# ledstripes.net
KiCad netlist of a schematic drawn in Altium Designer
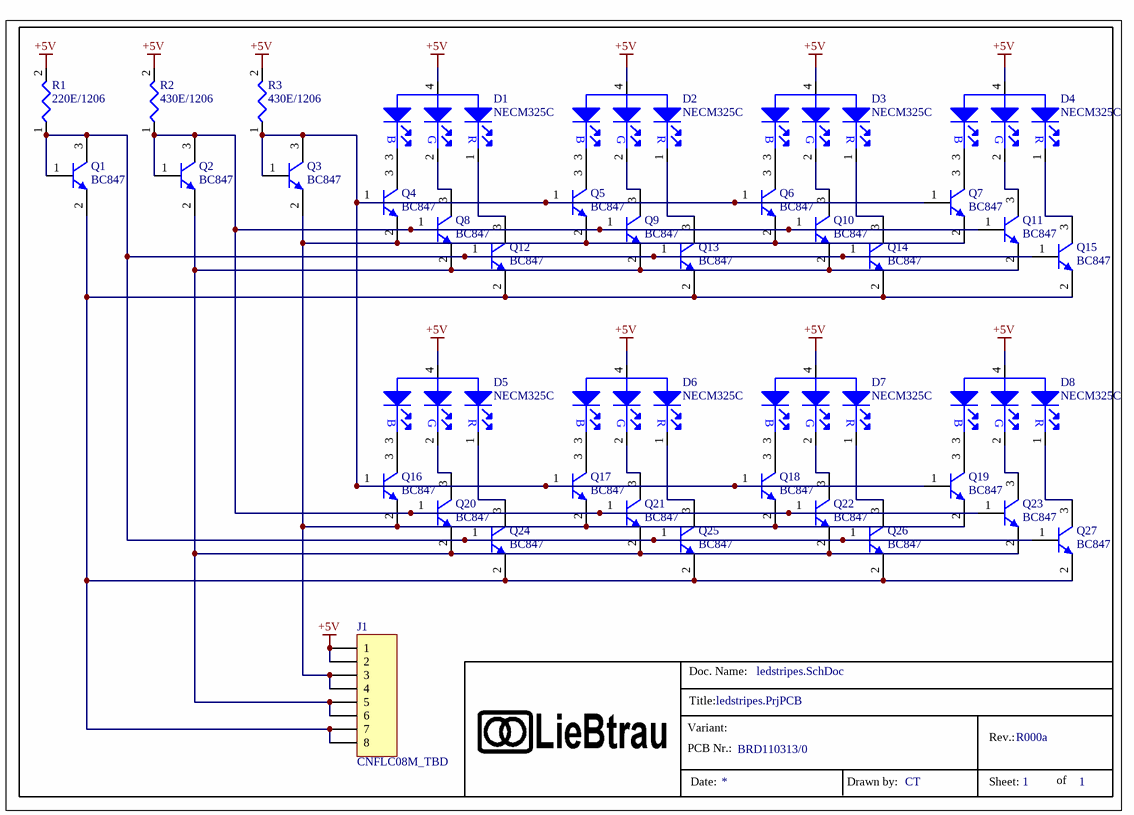
[diagram p0: ledstripes.SchDoc]

(export (version "E")
  (design (tool "Eeschema 10.0.6"))
  (components
    (comp (ref "D1")
      (value "NECM325C")
      (footprint "D_PLCC4")
      (fields (field (name "MANUFACTURER") "Nichia"))
      (libsource (lib "Testing") (part "D_LED_RGB"))
    )
    (comp (ref "D2")
      (value "NECM325C")
      (footprint "D_PLCC4")
      (fields (field (name "MANUFACTURER") "Nichia"))
      (libsource (lib "Testing") (part "D_LED_RGB"))
    )
    (comp (ref "D3")
      (value "NECM325C")
      (footprint "D_PLCC4")
      (fields (field (name "MANUFACTURER") "Nichia"))
      (libsource (lib "Testing") (part "D_LED_RGB"))
    )
    (comp (ref "D4")
      (value "NECM325C")
      (footprint "D_PLCC4")
      (fields (field (name "MANUFACTURER") "Nichia"))
      (libsource (lib "Testing") (part "D_LED_RGB"))
    )
    (comp (ref "D5")
      (value "NECM325C")
      (footprint "D_PLCC4")
      (fields (field (name "MANUFACTURER") "Nichia"))
      (libsource (lib "Testing") (part "D_LED_RGB"))
    )
    (comp (ref "D6")
      (value "NECM325C")
      (footprint "D_PLCC4")
      (fields (field (name "MANUFACTURER") "Nichia"))
      (libsource (lib "Testing") (part "D_LED_RGB"))
    )
    (comp (ref "D7")
      (value "NECM325C")
      (footprint "D_PLCC4")
      (fields (field (name "MANUFACTURER") "Nichia"))
      (libsource (lib "Testing") (part "D_LED_RGB"))
    )
    (comp (ref "D8")
      (value "NECM325C")
      (footprint "D_PLCC4")
      (fields (field (name "MANUFACTURER") "Nichia"))
      (libsource (lib "Testing") (part "D_LED_RGB"))
    )
    (comp (ref "J1")
      (value "CNFLC08M_TBD")
      (footprint "J_215079-8")
      (fields (field (name "PART NUMBER") "CNFLC08F_TBD"))
      (libsource (lib "Testing") (part "J_8P"))
    )
    (comp (ref "Q1")
      (value "BC847")
      (footprint "SOT23")
      (description "Amplifier Transistor NPN Silicon")
      (libsource (lib "Testing") (part "Q_NPN_1"))
    )
    (comp (ref "Q2")
      (value "BC847")
      (footprint "SOT23")
      (description "Amplifier Transistor NPN Silicon")
      (libsource (lib "Testing") (part "Q_NPN_1"))
    )
    (comp (ref "Q3")
      (value "BC847")
      (footprint "SOT23")
      (description "Amplifier Transistor NPN Silicon")
      (libsource (lib "Testing") (part "Q_NPN_1"))
    )
    (comp (ref "Q4")
      (value "BC847")
      (footprint "SOT23")
      (description "Amplifier Transistor NPN Silicon")
      (libsource (lib "Testing") (part "Q_NPN_1"))
    )
    (comp (ref "Q5")
      (value "BC847")
      (footprint "SOT23")
      (description "Amplifier Transistor NPN Silicon")
      (libsource (lib "Testing") (part "Q_NPN_1"))
    )
    (comp (ref "Q6")
      (value "BC847")
      (footprint "SOT23")
      (description "Amplifier Transistor NPN Silicon")
      (libsource (lib "Testing") (part "Q_NPN_1"))
    )
    (comp (ref "Q7")
      (value "BC847")
      (footprint "SOT23")
      (description "Amplifier Transistor NPN Silicon")
      (libsource (lib "Testing") (part "Q_NPN_1"))
    )
    (comp (ref "Q8")
      (value "BC847")
      (footprint "SOT23")
      (description "Amplifier Transistor NPN Silicon")
      (libsource (lib "Testing") (part "Q_NPN_1"))
    )
    (comp (ref "Q9")
      (value "BC847")
      (footprint "SOT23")
      (description "Amplifier Transistor NPN Silicon")
      (libsource (lib "Testing") (part "Q_NPN_1"))
    )
    (comp (ref "Q10")
      (value "BC847")
      (footprint "SOT23")
      (description "Amplifier Transistor NPN Silicon")
      (libsource (lib "Testing") (part "Q_NPN_1"))
    )
    (comp (ref "Q11")
      (value "BC847")
      (footprint "SOT23")
      (description "Amplifier Transistor NPN Silicon")
      (libsource (lib "Testing") (part "Q_NPN_1"))
    )
    (comp (ref "Q12")
      (value "BC847")
      (footprint "SOT23")
      (description "Amplifier Transistor NPN Silicon")
      (libsource (lib "Testing") (part "Q_NPN_1"))
    )
    (comp (ref "Q13")
      (value "BC847")
      (footprint "SOT23")
      (description "Amplifier Transistor NPN Silicon")
      (libsource (lib "Testing") (part "Q_NPN_1"))
    )
    (comp (ref "Q14")
      (value "BC847")
      (footprint "SOT23")
      (description "Amplifier Transistor NPN Silicon")
      (libsource (lib "Testing") (part "Q_NPN_1"))
    )
    (comp (ref "Q15")
      (value "BC847")
      (footprint "SOT23")
      (description "Amplifier Transistor NPN Silicon")
      (libsource (lib "Testing") (part "Q_NPN_1"))
    )
    (comp (ref "Q16")
      (value "BC847")
      (footprint "SOT23")
      (description "Amplifier Transistor NPN Silicon")
      (libsource (lib "Testing") (part "Q_NPN_1"))
    )
    (comp (ref "Q17")
      (value "BC847")
      (footprint "SOT23")
      (description "Amplifier Transistor NPN Silicon")
      (libsource (lib "Testing") (part "Q_NPN_1"))
    )
    (comp (ref "Q18")
      (value "BC847")
      (footprint "SOT23")
      (description "Amplifier Transistor NPN Silicon")
      (libsource (lib "Testing") (part "Q_NPN_1"))
    )
    (comp (ref "Q19")
      (value "BC847")
      (footprint "SOT23")
      (description "Amplifier Transistor NPN Silicon")
      (libsource (lib "Testing") (part "Q_NPN_1"))
    )
    (comp (ref "Q20")
      (value "BC847")
      (footprint "SOT23")
      (description "Amplifier Transistor NPN Silicon")
      (libsource (lib "Testing") (part "Q_NPN_1"))
    )
    (comp (ref "Q21")
      (value "BC847")
      (footprint "SOT23")
      (description "Amplifier Transistor NPN Silicon")
      (libsource (lib "Testing") (part "Q_NPN_1"))
    )
    (comp (ref "Q22")
      (value "BC847")
      (footprint "SOT23")
      (description "Amplifier Transistor NPN Silicon")
      (libsource (lib "Testing") (part "Q_NPN_1"))
    )
    (comp (ref "Q23")
      (value "BC847")
      (footprint "SOT23")
      (description "Amplifier Transistor NPN Silicon")
      (libsource (lib "Testing") (part "Q_NPN_1"))
    )
    (comp (ref "Q24")
      (value "BC847")
      (footprint "SOT23")
      (description "Amplifier Transistor NPN Silicon")
      (libsource (lib "Testing") (part "Q_NPN_1"))
    )
    (comp (ref "Q25")
      (value "BC847")
      (footprint "SOT23")
      (description "Amplifier Transistor NPN Silicon")
      (libsource (lib "Testing") (part "Q_NPN_1"))
    )
    (comp (ref "Q26")
      (value "BC847")
      (footprint "SOT23")
      (description "Amplifier Transistor NPN Silicon")
      (libsource (lib "Testing") (part "Q_NPN_1"))
    )
    (comp (ref "Q27")
      (value "BC847")
      (footprint "SOT23")
      (description "Amplifier Transistor NPN Silicon")
      (libsource (lib "Testing") (part "Q_NPN_1"))
    )
    (comp (ref "R1")
      (value "220E/1206")
      (footprint "R_1206")
      (description "Resistor")
      (fields (field (name "PART NUMBER") "YRES220_1206") (field (name "MANUFACTURER") "Yageo (Phycomp)"))
      (libsource (lib "Testing") (part "R_RES"))
    )
    (comp (ref "R2")
      (value "430E/1206")
      (footprint "R_1206")
      (description "Resistor")
      (fields (field (name "PART NUMBER") "YRES430E_TBD") (field (name "MANUFACTURER") "Welwyn"))
      (libsource (lib "Testing") (part "R_RES"))
    )
    (comp (ref "R3")
      (value "430E/1206")
      (footprint "R_1206")
      (description "Resistor")
      (fields (field (name "PART NUMBER") "YRES430E_TBD") (field (name "MANUFACTURER") "Welwyn"))
      (libsource (lib "Testing") (part "R_RES"))
    )
  )
  (nets
    (net (code "1") (name "+5V") (class "Default")
      (node (ref "D1") (pin "4") (pinfunction "A_4") (pintype "passive"))
      (node (ref "D2") (pin "4") (pinfunction "A_4") (pintype "passive"))
      (node (ref "D3") (pin "4") (pinfunction "A_4") (pintype "passive"))
      (node (ref "D4") (pin "4") (pinfunction "A_4") (pintype "passive"))
      (node (ref "D5") (pin "4") (pinfunction "A_4") (pintype "passive"))
      (node (ref "D6") (pin "4") (pinfunction "A_4") (pintype "passive"))
      (node (ref "D7") (pin "4") (pinfunction "A_4") (pintype "passive"))
      (node (ref "D8") (pin "4") (pinfunction "A_4") (pintype "passive"))
      (node (ref "J1") (pin "1") (pinfunction "1_1") (pintype "passive"))
      (node (ref "J1") (pin "2") (pinfunction "2_2") (pintype "passive"))
      (node (ref "R1") (pin "2") (pinfunction "2_2") (pintype "passive"))
      (node (ref "R2") (pin "2") (pinfunction "2_2") (pintype "passive"))
      (node (ref "R3") (pin "2") (pinfunction "2_2") (pintype "passive"))
    )
    (net (code "2") (name "Net-(Q1-B)") (class "Default")
      (node (ref "J1") (pin "7") (pinfunction "7_7") (pintype "passive"))
      (node (ref "J1") (pin "8") (pinfunction "8_8") (pintype "passive"))
      (node (ref "Q1") (pin "2") (pinfunction "B_2") (pintype "passive"))
      (node (ref "Q12") (pin "2") (pinfunction "B_2") (pintype "passive"))
      (node (ref "Q13") (pin "2") (pinfunction "B_2") (pintype "passive"))
      (node (ref "Q14") (pin "2") (pinfunction "B_2") (pintype "passive"))
      (node (ref "Q15") (pin "2") (pinfunction "B_2") (pintype "passive"))
      (node (ref "Q24") (pin "2") (pinfunction "B_2") (pintype "passive"))
      (node (ref "Q25") (pin "2") (pinfunction "B_2") (pintype "passive"))
      (node (ref "Q26") (pin "2") (pinfunction "B_2") (pintype "passive"))
      (node (ref "Q27") (pin "2") (pinfunction "B_2") (pintype "passive"))
    )
    (net (code "3") (name "Net-(Q1-C)") (class "Default")
      (node (ref "Q1") (pin "1") (pinfunction "C_1") (pintype "passive"))
      (node (ref "Q1") (pin "3") (pinfunction "E_3") (pintype "passive"))
      (node (ref "Q12") (pin "1") (pinfunction "C_1") (pintype "passive"))
      (node (ref "Q13") (pin "1") (pinfunction "C_1") (pintype "passive"))
      (node (ref "Q14") (pin "1") (pinfunction "C_1") (pintype "passive"))
      (node (ref "Q15") (pin "1") (pinfunction "C_1") (pintype "passive"))
      (node (ref "Q24") (pin "1") (pinfunction "C_1") (pintype "passive"))
      (node (ref "Q25") (pin "1") (pinfunction "C_1") (pintype "passive"))
      (node (ref "Q26") (pin "1") (pinfunction "C_1") (pintype "passive"))
      (node (ref "Q27") (pin "1") (pinfunction "C_1") (pintype "passive"))
      (node (ref "R1") (pin "1") (pinfunction "1_1") (pintype "passive"))
    )
    (net (code "4") (name "Net-(Q4-E)") (class "Default")
      (node (ref "D1") (pin "3") (pinfunction "C_3") (pintype "passive"))
      (node (ref "Q4") (pin "3") (pinfunction "E_3") (pintype "passive"))
    )
    (net (code "5") (name "Net-(Q5-E)") (class "Default")
      (node (ref "D2") (pin "3") (pinfunction "C_3") (pintype "passive"))
      (node (ref "Q5") (pin "3") (pinfunction "E_3") (pintype "passive"))
    )
    (net (code "6") (name "Net-(Q6-E)") (class "Default")
      (node (ref "D3") (pin "3") (pinfunction "C_3") (pintype "passive"))
      (node (ref "Q6") (pin "3") (pinfunction "E_3") (pintype "passive"))
    )
    (net (code "7") (name "Net-(Q7-E)") (class "Default")
      (node (ref "D4") (pin "3") (pinfunction "C_3") (pintype "passive"))
      (node (ref "Q7") (pin "3") (pinfunction "E_3") (pintype "passive"))
    )
    (net (code "8") (name "Net-(Q8-E)") (class "Default")
      (node (ref "D1") (pin "2") (pinfunction "C_2") (pintype "passive"))
      (node (ref "Q8") (pin "3") (pinfunction "E_3") (pintype "passive"))
    )
    (net (code "9") (name "Net-(Q9-E)") (class "Default")
      (node (ref "D2") (pin "2") (pinfunction "C_2") (pintype "passive"))
      (node (ref "Q9") (pin "3") (pinfunction "E_3") (pintype "passive"))
    )
    (net (code "10") (name "Net-(Q10-B)") (class "Default")
      (node (ref "J1") (pin "5") (pinfunction "5_5") (pintype "passive"))
      (node (ref "J1") (pin "6") (pinfunction "6_6") (pintype "passive"))
      (node (ref "Q10") (pin "2") (pinfunction "B_2") (pintype "passive"))
      (node (ref "Q11") (pin "2") (pinfunction "B_2") (pintype "passive"))
      (node (ref "Q2") (pin "2") (pinfunction "B_2") (pintype "passive"))
      (node (ref "Q20") (pin "2") (pinfunction "B_2") (pintype "passive"))
      (node (ref "Q21") (pin "2") (pinfunction "B_2") (pintype "passive"))
      (node (ref "Q22") (pin "2") (pinfunction "B_2") (pintype "passive"))
      (node (ref "Q23") (pin "2") (pinfunction "B_2") (pintype "passive"))
      (node (ref "Q8") (pin "2") (pinfunction "B_2") (pintype "passive"))
      (node (ref "Q9") (pin "2") (pinfunction "B_2") (pintype "passive"))
    )
    (net (code "11") (name "Net-(Q10-C)") (class "Default")
      (node (ref "Q10") (pin "1") (pinfunction "C_1") (pintype "passive"))
      (node (ref "Q11") (pin "1") (pinfunction "C_1") (pintype "passive"))
      (node (ref "Q2") (pin "1") (pinfunction "C_1") (pintype "passive"))
      (node (ref "Q2") (pin "3") (pinfunction "E_3") (pintype "passive"))
      (node (ref "Q20") (pin "1") (pinfunction "C_1") (pintype "passive"))
      (node (ref "Q21") (pin "1") (pinfunction "C_1") (pintype "passive"))
      (node (ref "Q22") (pin "1") (pinfunction "C_1") (pintype "passive"))
      (node (ref "Q23") (pin "1") (pinfunction "C_1") (pintype "passive"))
      (node (ref "Q8") (pin "1") (pinfunction "C_1") (pintype "passive"))
      (node (ref "Q9") (pin "1") (pinfunction "C_1") (pintype "passive"))
      (node (ref "R2") (pin "1") (pinfunction "1_1") (pintype "passive"))
    )
    (net (code "12") (name "Net-(Q10-E)") (class "Default")
      (node (ref "D3") (pin "2") (pinfunction "C_2") (pintype "passive"))
      (node (ref "Q10") (pin "3") (pinfunction "E_3") (pintype "passive"))
    )
    (net (code "13") (name "Net-(Q11-E)") (class "Default")
      (node (ref "D4") (pin "2") (pinfunction "C_2") (pintype "passive"))
      (node (ref "Q11") (pin "3") (pinfunction "E_3") (pintype "passive"))
    )
    (net (code "14") (name "Net-(Q12-E)") (class "Default")
      (node (ref "D1") (pin "1") (pinfunction "C_1") (pintype "passive"))
      (node (ref "Q12") (pin "3") (pinfunction "E_3") (pintype "passive"))
    )
    (net (code "15") (name "Net-(Q13-E)") (class "Default")
      (node (ref "D2") (pin "1") (pinfunction "C_1") (pintype "passive"))
      (node (ref "Q13") (pin "3") (pinfunction "E_3") (pintype "passive"))
    )
    (net (code "16") (name "Net-(Q14-E)") (class "Default")
      (node (ref "D3") (pin "1") (pinfunction "C_1") (pintype "passive"))
      (node (ref "Q14") (pin "3") (pinfunction "E_3") (pintype "passive"))
    )
    (net (code "17") (name "Net-(Q15-E)") (class "Default")
      (node (ref "D4") (pin "1") (pinfunction "C_1") (pintype "passive"))
      (node (ref "Q15") (pin "3") (pinfunction "E_3") (pintype "passive"))
    )
    (net (code "18") (name "Net-(Q16-B)") (class "Default")
      (node (ref "J1") (pin "3") (pinfunction "3_3") (pintype "passive"))
      (node (ref "J1") (pin "4") (pinfunction "4_4") (pintype "passive"))
      (node (ref "Q16") (pin "2") (pinfunction "B_2") (pintype "passive"))
      (node (ref "Q17") (pin "2") (pinfunction "B_2") (pintype "passive"))
      (node (ref "Q18") (pin "2") (pinfunction "B_2") (pintype "passive"))
      (node (ref "Q19") (pin "2") (pinfunction "B_2") (pintype "passive"))
      (node (ref "Q3") (pin "2") (pinfunction "B_2") (pintype "passive"))
      (node (ref "Q4") (pin "2") (pinfunction "B_2") (pintype "passive"))
      (node (ref "Q5") (pin "2") (pinfunction "B_2") (pintype "passive"))
      (node (ref "Q6") (pin "2") (pinfunction "B_2") (pintype "passive"))
      (node (ref "Q7") (pin "2") (pinfunction "B_2") (pintype "passive"))
    )
    (net (code "19") (name "Net-(Q16-C)") (class "Default")
      (node (ref "Q16") (pin "1") (pinfunction "C_1") (pintype "passive"))
      (node (ref "Q17") (pin "1") (pinfunction "C_1") (pintype "passive"))
      (node (ref "Q18") (pin "1") (pinfunction "C_1") (pintype "passive"))
      (node (ref "Q19") (pin "1") (pinfunction "C_1") (pintype "passive"))
      (node (ref "Q3") (pin "1") (pinfunction "C_1") (pintype "passive"))
      (node (ref "Q3") (pin "3") (pinfunction "E_3") (pintype "passive"))
      (node (ref "Q4") (pin "1") (pinfunction "C_1") (pintype "passive"))
      (node (ref "Q5") (pin "1") (pinfunction "C_1") (pintype "passive"))
      (node (ref "Q6") (pin "1") (pinfunction "C_1") (pintype "passive"))
      (node (ref "Q7") (pin "1") (pinfunction "C_1") (pintype "passive"))
      (node (ref "R3") (pin "1") (pinfunction "1_1") (pintype "passive"))
    )
    (net (code "20") (name "Net-(Q16-E)") (class "Default")
      (node (ref "D5") (pin "3") (pinfunction "C_3") (pintype "passive"))
      (node (ref "Q16") (pin "3") (pinfunction "E_3") (pintype "passive"))
    )
    (net (code "21") (name "Net-(Q17-E)") (class "Default")
      (node (ref "D6") (pin "3") (pinfunction "C_3") (pintype "passive"))
      (node (ref "Q17") (pin "3") (pinfunction "E_3") (pintype "passive"))
    )
    (net (code "22") (name "Net-(Q18-E)") (class "Default")
      (node (ref "D7") (pin "3") (pinfunction "C_3") (pintype "passive"))
      (node (ref "Q18") (pin "3") (pinfunction "E_3") (pintype "passive"))
    )
    (net (code "23") (name "Net-(Q19-E)") (class "Default")
      (node (ref "D8") (pin "3") (pinfunction "C_3") (pintype "passive"))
      (node (ref "Q19") (pin "3") (pinfunction "E_3") (pintype "passive"))
    )
    (net (code "24") (name "Net-(Q20-E)") (class "Default")
      (node (ref "D5") (pin "2") (pinfunction "C_2") (pintype "passive"))
      (node (ref "Q20") (pin "3") (pinfunction "E_3") (pintype "passive"))
    )
    (net (code "25") (name "Net-(Q21-E)") (class "Default")
      (node (ref "D6") (pin "2") (pinfunction "C_2") (pintype "passive"))
      (node (ref "Q21") (pin "3") (pinfunction "E_3") (pintype "passive"))
    )
    (net (code "26") (name "Net-(Q22-E)") (class "Default")
      (node (ref "D7") (pin "2") (pinfunction "C_2") (pintype "passive"))
      (node (ref "Q22") (pin "3") (pinfunction "E_3") (pintype "passive"))
    )
    (net (code "27") (name "Net-(Q23-E)") (class "Default")
      (node (ref "D8") (pin "2") (pinfunction "C_2") (pintype "passive"))
      (node (ref "Q23") (pin "3") (pinfunction "E_3") (pintype "passive"))
    )
    (net (code "28") (name "Net-(Q24-E)") (class "Default")
      (node (ref "D5") (pin "1") (pinfunction "C_1") (pintype "passive"))
      (node (ref "Q24") (pin "3") (pinfunction "E_3") (pintype "passive"))
    )
    (net (code "29") (name "Net-(Q25-E)") (class "Default")
      (node (ref "D6") (pin "1") (pinfunction "C_1") (pintype "passive"))
      (node (ref "Q25") (pin "3") (pinfunction "E_3") (pintype "passive"))
    )
    (net (code "30") (name "Net-(Q26-E)") (class "Default")
      (node (ref "D7") (pin "1") (pinfunction "C_1") (pintype "passive"))
      (node (ref "Q26") (pin "3") (pinfunction "E_3") (pintype "passive"))
    )
    (net (code "31") (name "Net-(Q27-E)") (class "Default")
      (node (ref "D8") (pin "1") (pinfunction "C_1") (pintype "passive"))
      (node (ref "Q27") (pin "3") (pinfunction "E_3") (pintype "passive"))
    )
  )
)
